# HBridge_v1.net
KiCad netlist of a schematic drawn in EAGLE
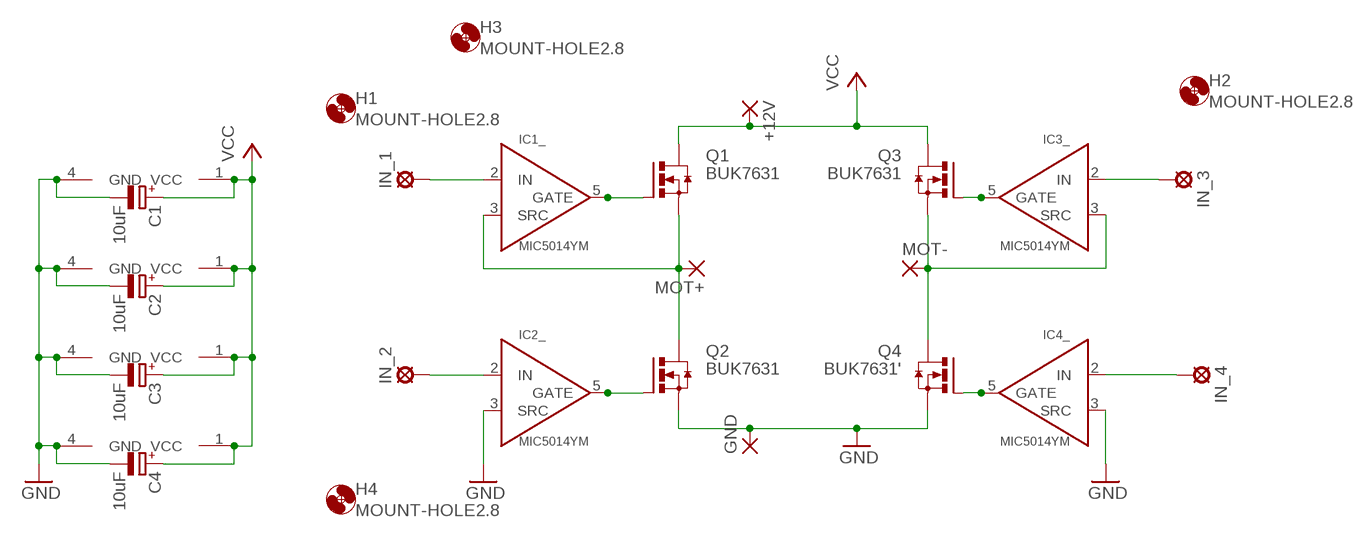
[diagram p0: schematic, sheet 1]

(export (version "E")
  (design (tool "Eeschema 10.0.6"))
  (components
    (comp (ref "+12V")
      (value "WIREPAD4,16O1,6")
      (footprint "eagle-import:4,16O1,6")
      (libsource (lib "eagle-import") (part "WIREPAD4,16O1,6"))
    )
    (comp (ref "C1")
      (value "10uF")
      (footprint "eagle-import:UD-4X5,8_NICHICON")
      (libsource (lib "eagle-import") (part "CPOL-EUUD-4X5,8"))
    )
    (comp (ref "C2")
      (value "10uF")
      (footprint "eagle-import:UD-4X5,8_NICHICON")
      (libsource (lib "eagle-import") (part "CPOL-EUUD-4X5,8"))
    )
    (comp (ref "C3")
      (value "10uF")
      (footprint "eagle-import:UD-4X5,8_NICHICON")
      (libsource (lib "eagle-import") (part "CPOL-EUUD-4X5,8"))
    )
    (comp (ref "C4")
      (value "10uF")
      (footprint "eagle-import:UD-4X5,8_NICHICON")
      (libsource (lib "eagle-import") (part "CPOL-EUUD-4X5,8"))
    )
    (comp (ref "GND")
      (value "WIREPAD4,16O1,6")
      (footprint "eagle-import:4,16O1,6")
      (libsource (lib "eagle-import") (part "WIREPAD4,16O1,6"))
    )
    (comp (ref "H1")
      (value "MOUNT-HOLE2.8")
      (footprint "eagle-import:2,8")
      (libsource (lib "eagle-import") (part "MOUNT-HOLE2.8"))
    )
    (comp (ref "H2")
      (value "MOUNT-HOLE2.8")
      (footprint "eagle-import:2,8")
      (libsource (lib "eagle-import") (part "MOUNT-HOLE2.8"))
    )
    (comp (ref "H3")
      (value "MOUNT-HOLE2.8")
      (footprint "eagle-import:2,8")
      (libsource (lib "eagle-import") (part "MOUNT-HOLE2.8"))
    )
    (comp (ref "H4")
      (value "MOUNT-HOLE2.8")
      (footprint "eagle-import:2,8")
      (libsource (lib "eagle-import") (part "MOUNT-HOLE2.8"))
    )
    (comp (ref "IC1")
      (value "MIC5014YM")
      (footprint "eagle-import:SO8")
      (libsource (lib "eagle-import") (part "MIC5014YM"))
    )
    (comp (ref "IC2")
      (value "MIC5014YM")
      (footprint "eagle-import:SO8")
      (libsource (lib "eagle-import") (part "MIC5014YM"))
    )
    (comp (ref "IC3")
      (value "MIC5014YM")
      (footprint "eagle-import:SO8")
      (libsource (lib "eagle-import") (part "MIC5014YM"))
    )
    (comp (ref "IC4")
      (value "MIC5014YM")
      (footprint "eagle-import:SO8")
      (libsource (lib "eagle-import") (part "MIC5014YM"))
    )
    (comp (ref "IN_1")
      (value "LSP11")
      (footprint "eagle-import:LSP11")
      (libsource (lib "eagle-import") (part "LSP11"))
    )
    (comp (ref "IN_2")
      (value "LSP11")
      (footprint "eagle-import:LSP11")
      (libsource (lib "eagle-import") (part "LSP11"))
    )
    (comp (ref "IN_3")
      (value "LSP11")
      (footprint "eagle-import:LSP11")
      (libsource (lib "eagle-import") (part "LSP11"))
    )
    (comp (ref "IN_4")
      (value "LSP11")
      (footprint "eagle-import:LSP11")
      (libsource (lib "eagle-import") (part "LSP11"))
    )
    (comp (ref "MOT+")
      (value "WIREPAD4,16O1,6")
      (footprint "eagle-import:4,16O1,6")
      (libsource (lib "eagle-import") (part "WIREPAD4,16O1,6"))
    )
    (comp (ref "MOT-")
      (value "WIREPAD4,16O1,6")
      (footprint "eagle-import:4,16O1,6")
      (libsource (lib "eagle-import") (part "WIREPAD4,16O1,6"))
    )
    (comp (ref "Q1")
      (value "BUK7631")
      (footprint "eagle-import:D2PAK_TO263")
      (libsource (lib "eagle-import") (part "BUK7631-100EBUK7631-100E"))
    )
    (comp (ref "Q2")
      (value "BUK7631")
      (footprint "eagle-import:D2PAK_TO263")
      (libsource (lib "eagle-import") (part "BUK7631-100EBUK7631-100E"))
    )
    (comp (ref "Q3")
      (value "BUK7631")
      (footprint "eagle-import:D2PAK_TO263")
      (libsource (lib "eagle-import") (part "BUK7631-100EBUK7631-100E"))
    )
    (comp (ref "Q4")
      (value "BUK7631'")
      (footprint "eagle-import:D2PAK_TO263")
      (libsource (lib "eagle-import") (part "BUK7631-100EBUK7631-100E"))
    )
  )
  (nets
    (net (code "1") (name "GND") (class "Default")
      (node (ref "C1") (pin "-") (pinfunction "-_-") (pintype "passive"))
      (node (ref "C2") (pin "-") (pinfunction "-_-") (pintype "passive"))
      (node (ref "C3") (pin "-") (pinfunction "-_-") (pintype "passive"))
      (node (ref "C4") (pin "-") (pinfunction "-_-") (pintype "passive"))
      (node (ref "GND") (pin "1") (pinfunction "P_1") (pintype "passive"))
      (node (ref "IC1") (pin "4") (pinfunction "GND_4") (pintype "power_in"))
      (node (ref "IC2") (pin "3") (pinfunction "SRC_3") (pintype "passive"))
      (node (ref "IC2") (pin "4") (pinfunction "GND_4") (pintype "power_in"))
      (node (ref "IC3") (pin "4") (pinfunction "GND_4") (pintype "power_in"))
      (node (ref "IC4") (pin "3") (pinfunction "SRC_3") (pintype "passive"))
      (node (ref "IC4") (pin "4") (pinfunction "GND_4") (pintype "power_in"))
      (node (ref "Q2") (pin "3") (pinfunction "S_3") (pintype "passive"))
      (node (ref "Q4") (pin "3") (pinfunction "S_3") (pintype "passive"))
    )
    (net (code "2") (name "Net-(IC1B-GATE)") (class "Default")
      (node (ref "IC1") (pin "5") (pinfunction "GATE_5") (pintype "passive"))
      (node (ref "Q1") (pin "1") (pinfunction "G_1") (pintype "passive"))
    )
    (net (code "3") (name "Net-(IC1B-IN)") (class "Default")
      (node (ref "IC1") (pin "2") (pinfunction "IN_2") (pintype "passive"))
      (node (ref "IN_1") (pin "MP") (pinfunction "MP_MP") (pintype "passive"))
    )
    (net (code "4") (name "Net-(IC1B-SRC)") (class "Default")
      (node (ref "IC1") (pin "3") (pinfunction "SRC_3") (pintype "passive"))
      (node (ref "MOT+") (pin "1") (pinfunction "P_1") (pintype "passive"))
      (node (ref "Q1") (pin "3") (pinfunction "S_3") (pintype "passive"))
      (node (ref "Q2") (pin "4") (pinfunction "D_4") (pintype "passive"))
    )
    (net (code "5") (name "Net-(IC2B-GATE)") (class "Default")
      (node (ref "IC2") (pin "5") (pinfunction "GATE_5") (pintype "passive"))
      (node (ref "Q2") (pin "1") (pinfunction "G_1") (pintype "passive"))
    )
    (net (code "6") (name "Net-(IC2B-IN)") (class "Default")
      (node (ref "IC2") (pin "2") (pinfunction "IN_2") (pintype "passive"))
      (node (ref "IN_2") (pin "MP") (pinfunction "MP_MP") (pintype "passive"))
    )
    (net (code "7") (name "Net-(IC3B-GATE)") (class "Default")
      (node (ref "IC3") (pin "5") (pinfunction "GATE_5") (pintype "passive"))
      (node (ref "Q3") (pin "1") (pinfunction "G_1") (pintype "passive"))
    )
    (net (code "8") (name "Net-(IC3B-IN)") (class "Default")
      (node (ref "IC3") (pin "2") (pinfunction "IN_2") (pintype "passive"))
      (node (ref "IN_3") (pin "MP") (pinfunction "MP_MP") (pintype "passive"))
    )
    (net (code "9") (name "Net-(IC3B-SRC)") (class "Default")
      (node (ref "IC3") (pin "3") (pinfunction "SRC_3") (pintype "passive"))
      (node (ref "MOT-") (pin "1") (pinfunction "P_1") (pintype "passive"))
      (node (ref "Q3") (pin "3") (pinfunction "S_3") (pintype "passive"))
      (node (ref "Q4") (pin "4") (pinfunction "D_4") (pintype "passive"))
    )
    (net (code "10") (name "Net-(IC4B-GATE)") (class "Default")
      (node (ref "IC4") (pin "5") (pinfunction "GATE_5") (pintype "passive"))
      (node (ref "Q4") (pin "1") (pinfunction "G_1") (pintype "passive"))
    )
    (net (code "11") (name "Net-(IC4B-IN)") (class "Default")
      (node (ref "IC4") (pin "2") (pinfunction "IN_2") (pintype "passive"))
      (node (ref "IN_4") (pin "MP") (pinfunction "MP_MP") (pintype "passive"))
    )
    (net (code "12") (name "VCC") (class "Default")
      (node (ref "+12V") (pin "1") (pinfunction "P_1") (pintype "passive"))
      (node (ref "C1") (pin "+") (pinfunction "+_+") (pintype "passive"))
      (node (ref "C2") (pin "+") (pinfunction "+_+") (pintype "passive"))
      (node (ref "C3") (pin "+") (pinfunction "+_+") (pintype "passive"))
      (node (ref "C4") (pin "+") (pinfunction "+_+") (pintype "passive"))
      (node (ref "IC1") (pin "1") (pinfunction "VCC_1") (pintype "power_in"))
      (node (ref "IC2") (pin "1") (pinfunction "VCC_1") (pintype "power_in"))
      (node (ref "IC3") (pin "1") (pinfunction "VCC_1") (pintype "power_in"))
      (node (ref "IC4") (pin "1") (pinfunction "VCC_1") (pintype "power_in"))
      (node (ref "Q1") (pin "4") (pinfunction "D_4") (pintype "passive"))
      (node (ref "Q3") (pin "4") (pinfunction "D_4") (pintype "passive"))
    )
  )
)
